# 5V_Buck.net
KiCad netlist of a schematic drawn in Altium Designer
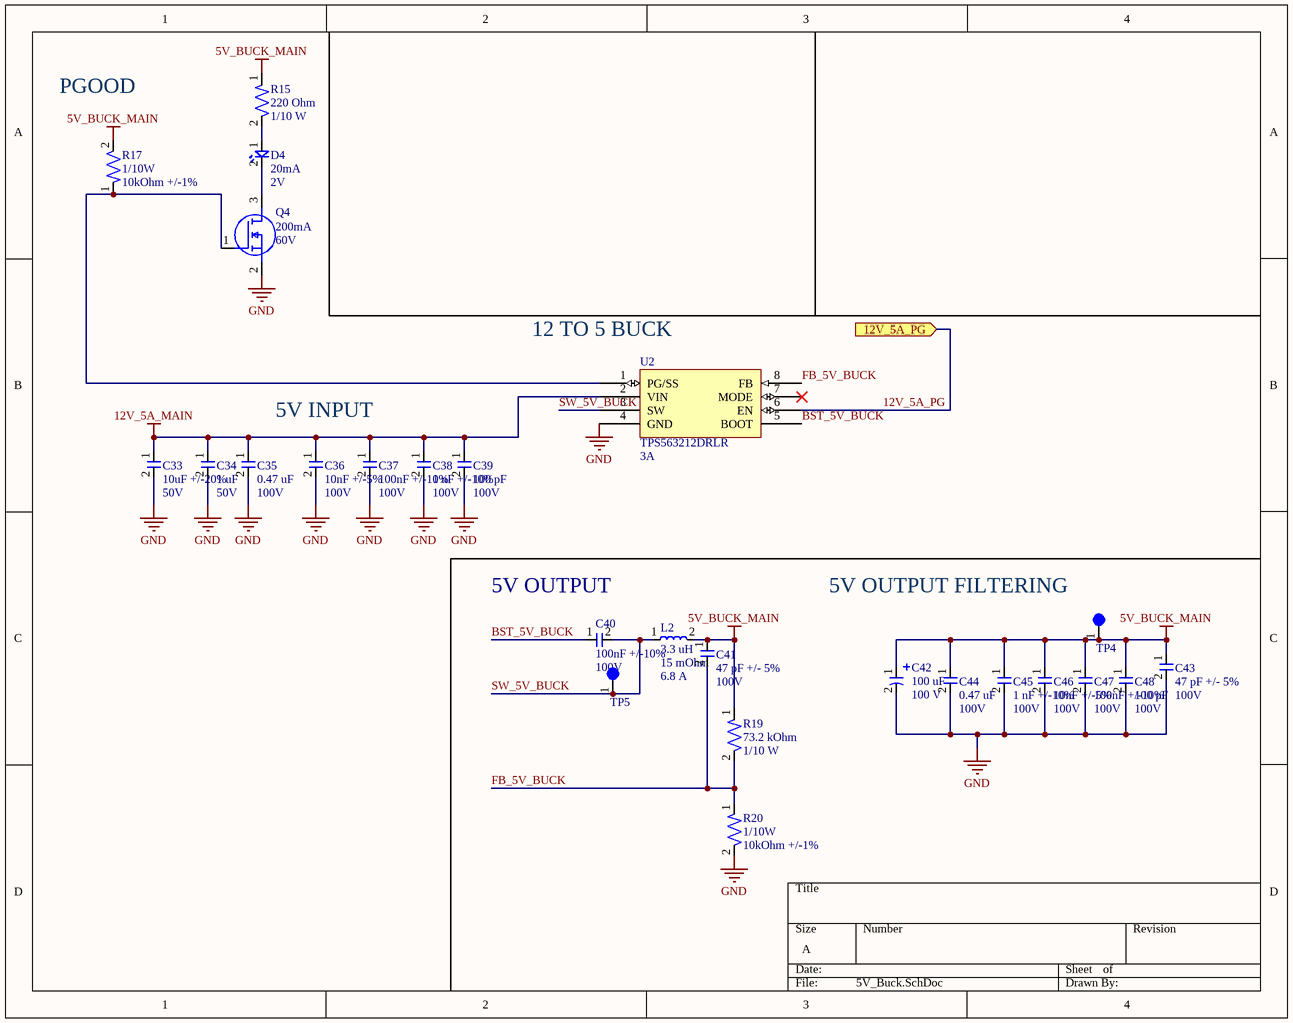
[diagram p0: 5V_Buck.SchDoc]

(export (version "E")
  (design (tool "Eeschema 10.0.6"))
  (components
    (comp (ref "C33")
      (value "CL31B106KBHNNNE")
      (footprint "CAP-1206")
      (description "10 µF ±10% 50V Ceramic Capacitor X7R 1206 (3216 Metric)")
      (fields
        (field (name "MANUFACTURER") "Samsung Electro-Mechanics")
        (field (name "CAPACITANCE") "10uF +/-20%")
        (field (name "VOLTAGE RATING") "50V")
      )
      (libsource (lib "MasterLib") (part "CAP-10U-0001"))
    )
    (comp (ref "C34")
      (value "UMK107AB7105KA-T")
      (footprint "CAP-0603")
      (description "1 µF ±10% 50V Ceramic Capacitor X7R 0603 (1608 Metric)")
      (fields (field (name "CAPACITANCE") "1 uF") (field (name "VOLTAGE") "50V"))
      (libsource (lib "MasterLib") (part "CAP-1U-0002"))
    )
    (comp (ref "C35")
      (value "KAM21KR72A474KL")
      (footprint "CAP-0805")
      (description "0.47 µF ±10% 100V Ceramic Capacitor X7R 0805 (2012 Metric)")
      (fields
        (field (name "TOLERANCE") "+/- 10%")
        (field (name "CAPACITANCE") "0.47 uF")
        (field (name "VOLTAGE") "100V")
      )
      (libsource (lib "MasterLib") (part "CAP-0.47U-0001"))
    )
    (comp (ref "C36")
      (value "C1608C0G2A103J080AC")
      (footprint "CAP-0603")
      (description "CAP CER 10000PF 100V C0G 0603")
      (fields
        (field (name "MANUFACTURER") "TDK Corporation")
        (field (name "CAPACITANCE") "10nF +/-5%")
        (field (name "VOLTAGE RATING") "100V")
      )
      (libsource (lib "MasterLib") (part "CAP-10N-0002"))
    )
    (comp (ref "C37")
      (value "CC0603KRX7R0BB104")
      (footprint "CAP-0603")
      (description "CAP CER 0.1UF 100V X7R 0603")
      (fields
        (field (name "MANUFACTURER") "YAGEO")
        (field (name "CAPACITANCE") "100nF +/-10%")
        (field (name "VOLTAGE RATING") "100V")
      )
      (libsource (lib "MasterLib") (part "CAP-100N-0001"))
    )
    (comp (ref "C38")
      (value "C0603Y102K1RAC7867")
      (footprint "CAP-0603")
      (description "1000 pF ±10% 100V Ceramic Capacitor X7R 0603 (1608 Metric)")
      (fields (field (name "CAPACITANCE") "1 nF +/-10%") (field (name "VOLTAGE") "100V"))
      (libsource (lib "MasterLib") (part "CAP-1N-0001"))
    )
    (comp (ref "C39")
      (value "0603N101J101CT")
      (footprint "CAP-0603")
      (description "100 pF ±5% 100V Ceramic Capacitor C0G, NP0 0603 (1608 Metric)")
      (fields
        (field (name "TOLERANCE") "+/-5%")
        (field (name "CAPACITANCE") "100 pF")
        (field (name "VOLTAGE") "100V")
      )
      (libsource (lib "MasterLib") (part "CAP-100P-0002"))
    )
    (comp (ref "C40")
      (value "CC0603KRX7R0BB104")
      (footprint "CAP-0603")
      (description "CAP CER 0.1UF 100V X7R 0603")
      (fields
        (field (name "MANUFACTURER") "YAGEO")
        (field (name "CAPACITANCE") "100nF +/-10%")
        (field (name "VOLTAGE RATING") "100V")
      )
      (libsource (lib "MasterLib") (part "CAP-100N-0001"))
    )
    (comp (ref "C41")
      (value "7447798111")
      (footprint "CAP-0603")
      (description "47 pF ±5% 100V Ceramic Capacitor C0G, NP0 0603 (1608 Metric)")
      (fields (field (name "CAPACITANCE") "47 pF +/- 5%") (field (name "VOLTAGE RATING") "100V"))
      (libsource (lib "MasterLib") (part "CAP-47P-0001"))
    )
    (comp (ref "C42")
      (value "100SEV100M12.5X16")
      (footprint "ELEC-100U-0001")
      (description "100 µF 100 V Aluminum Electrolytic Capacitors Radial, Can - SMD 2000 Hrs @ 85°C")
      (fields
        (field (name "MANUFACTURER") "Rubycon")
        (field (name "TOLERANCE") "+/- 20%")
        (field (name "CAPACITANCE") "100 uF")
        (field (name "VOLTAGE") "100 V")
      )
      (libsource (lib "MasterLib") (part "ELEC-100U-0001"))
    )
    (comp (ref "C43")
      (value "7447798111")
      (footprint "CAP-0603")
      (description "47 pF ±5% 100V Ceramic Capacitor C0G, NP0 0603 (1608 Metric)")
      (fields (field (name "CAPACITANCE") "47 pF +/- 5%") (field (name "VOLTAGE RATING") "100V"))
      (libsource (lib "MasterLib") (part "CAP-47P-0001"))
    )
    (comp (ref "C44")
      (value "KAM21KR72A474KL")
      (footprint "CAP-0805")
      (description "0.47 µF ±10% 100V Ceramic Capacitor X7R 0805 (2012 Metric)")
      (fields
        (field (name "TOLERANCE") "+/- 10%")
        (field (name "CAPACITANCE") "0.47 uF")
        (field (name "VOLTAGE") "100V")
      )
      (libsource (lib "MasterLib") (part "CAP-0.47U-0001"))
    )
    (comp (ref "C45")
      (value "C0603Y102K1RAC7867")
      (footprint "CAP-0603")
      (description "1000 pF ±10% 100V Ceramic Capacitor X7R 0603 (1608 Metric)")
      (fields (field (name "CAPACITANCE") "1 nF +/-10%") (field (name "VOLTAGE") "100V"))
      (libsource (lib "MasterLib") (part "CAP-1N-0001"))
    )
    (comp (ref "C46")
      (value "C1608C0G2A103J080AC")
      (footprint "CAP-0603")
      (description "CAP CER 10000PF 100V C0G 0603")
      (fields
        (field (name "MANUFACTURER") "TDK Corporation")
        (field (name "CAPACITANCE") "10nF +/-5%")
        (field (name "VOLTAGE RATING") "100V")
      )
      (libsource (lib "MasterLib") (part "CAP-10N-0002"))
    )
    (comp (ref "C47")
      (value "CC0603KRX7R0BB104")
      (footprint "CAP-0603")
      (description "CAP CER 0.1UF 100V X7R 0603")
      (fields
        (field (name "MANUFACTURER") "YAGEO")
        (field (name "CAPACITANCE") "100nF +/-10%")
        (field (name "VOLTAGE RATING") "100V")
      )
      (libsource (lib "MasterLib") (part "CAP-100N-0001"))
    )
    (comp (ref "C48")
      (value "0603N101J101CT")
      (footprint "CAP-0603")
      (description "100 pF ±5% 100V Ceramic Capacitor C0G, NP0 0603 (1608 Metric)")
      (fields
        (field (name "TOLERANCE") "+/-5%")
        (field (name "CAPACITANCE") "100 pF")
        (field (name "VOLTAGE") "100V")
      )
      (libsource (lib "MasterLib") (part "CAP-100P-0002"))
    )
    (comp (ref "D4")
      (value "150060AS75000")
      (footprint "LED-0603")
      (description "CAP CER 0.1UF 100V X7R 0603")
      (fields
        (field (name "MANUFACTURER") "Wurth Electronik")
        (field (name "CURRENT RATING") "20mA")
        (field (name "VF") "2V")
      )
      (libsource (lib "MasterLib") (part "LED_Amber_0001"))
    )
    (comp (ref "L2")
      (value "SRR1240-3R3Y")
      (footprint "PWRIND-3.3U-0003")
      (description "3.3 µH Shielded Drum Core, Wirewound Inductor 6.8 A 15mOhm Max Nonstandard")
      (fields
        (field (name "TOLERANCE") "30%")
        (field (name "INDUCTANCE") "3.3 uH")
        (field (name "DCR") "15 mOhm")
        (field (name "DCI") "6.8 A")
      )
      (libsource (lib "MasterLib") (part "PWRIND-3.3U-0003"))
    )
    (comp (ref "Q4")
      (value "T2N7002AK,LM")
      (footprint "NMOS-SOT23-3")
      (description "MOSFET N-CH 60V 200MA SOT23")
      (fields
        (field (name "MANUFACTURER") "Toshiba")
        (field (name "ID-CONTINUOUS") "200mA")
        (field (name "VDS-MAX") "60V")
      )
      (libsource (lib "MasterLib") (part "NMOS-200MA-0001"))
    )
    (comp (ref "R15")
      (value "CRGCQ0603J220R")
      (footprint "RES-0603")
      (fields
        (field (name "TOLERANCE") "+/- 5%")
        (field (name "RESISTANCE") "220 Ohm")
        (field (name "POWER") "1/10 W")
      )
      (libsource (lib "MasterLib") (part "RES-220-003"))
    )
    (comp (ref "R17")
      (value "RC0603FR-0710KP")
      (footprint "RES-0603")
      (description "RES SMD 10K OHM 1% 1/10W 0603")
      (fields
        (field (name "MANUFACTURER") "YAGEO")
        (field (name "POWER RATING") "1/10W")
        (field (name "RESISTANCE") "10kOhm +/-1%")
      )
      (libsource (lib "MasterLib") (part "RES-10K-0002"))
    )
    (comp (ref "R19")
      (value "RC0603FR-0773K2L")
      (footprint "RES-0603")
      (description "73.2 kOhms ±1% 0.1W, 1/10W Chip Resistor 0603 (1608 Metric) Moisture Resistant Thick Film")
      (fields
        (field (name "TOLERANCE") "1%")
        (field (name "RESISTANCE") "73.2 kOhm")
        (field (name "POWER") "1/10 W")
      )
      (libsource (lib "MasterLib") (part "RES-73.2K-0001"))
    )
    (comp (ref "R20")
      (value "RC0603FR-0710KP")
      (footprint "RES-0603")
      (description "RES SMD 10K OHM 1% 1/10W 0603")
      (fields
        (field (name "MANUFACTURER") "YAGEO")
        (field (name "POWER RATING") "1/10W")
        (field (name "RESISTANCE") "10kOhm +/-1%")
      )
      (libsource (lib "MasterLib") (part "RES-10K-0002"))
    )
    (comp (ref "TP4")
      (value "5003")
      (footprint "TEST-POINT-0001")
      (description "Oranange PC Test Point, Miniature Phoisphor Bronze Silver Plating Through Hole Mounting Type")
      (libsource (lib "MasterLib") (part "TEST-POINT-0001"))
    )
    (comp (ref "TP5")
      (value "5003")
      (footprint "TEST-POINT-0001")
      (description "Oranange PC Test Point, Miniature Phoisphor Bronze Silver Plating Through Hole Mounting Type")
      (libsource (lib "MasterLib") (part "TEST-POINT-0001"))
    )
    (comp (ref "U2")
      (value "TPS563212DRLR")
      (footprint "IC-SOT583")
      (description "Buck Switching Regulator IC Positive Adjustable 0.6V 1 Output 3A SOT-583")
      (fields (field (name "MANUFACTURER") "Texaas Instruments") (field (name "CURRENT") "3A"))
      (libsource (lib "MasterLib") (part "IC-BUCK-0008"))
    )
  )
  (nets
    (net (code "1") (name "/12V_5A_PG") (class "Default")
      (node (ref "U2") (pin "6") (pinfunction "EN_6") (pintype "bidirectional"))
    )
    (net (code "2") (name "/BST_5V_BUCK") (class "Default")
      (node (ref "C40") (pin "1") (pinfunction "1_1") (pintype "passive"))
      (node (ref "U2") (pin "5") (pinfunction "BOOT_5") (pintype "power_in"))
    )
    (net (code "3") (name "/FB_5V_BUCK") (class "Default")
      (node (ref "C41") (pin "2") (pinfunction "2_2") (pintype "passive"))
      (node (ref "R19") (pin "2") (pinfunction "2_2") (pintype "passive"))
      (node (ref "R20") (pin "1") (pinfunction "1_1") (pintype "passive"))
      (node (ref "U2") (pin "8") (pinfunction "FB_8") (pintype "input"))
    )
    (net (code "4") (name "/SW_5V_BUCK") (class "Default")
      (node (ref "C40") (pin "2") (pinfunction "2_2") (pintype "passive"))
      (node (ref "L2") (pin "1") (pinfunction "1_1") (pintype "passive"))
      (node (ref "TP5") (pin "1") (pinfunction "0_1") (pintype "passive"))
      (node (ref "U2") (pin "3") (pinfunction "SW_3") (pintype "power_in"))
    )
    (net (code "5") (name "5V_BUCK_MAIN") (class "Default")
      (node (ref "C41") (pin "1") (pinfunction "1_1") (pintype "passive"))
      (node (ref "C42") (pin "1") (pinfunction "1_1") (pintype "passive"))
      (node (ref "C43") (pin "1") (pinfunction "1_1") (pintype "passive"))
      (node (ref "C44") (pin "1") (pinfunction "1_1") (pintype "passive"))
      (node (ref "C45") (pin "1") (pinfunction "1_1") (pintype "passive"))
      (node (ref "C46") (pin "1") (pinfunction "1_1") (pintype "passive"))
      (node (ref "C47") (pin "1") (pinfunction "1_1") (pintype "passive"))
      (node (ref "C48") (pin "1") (pinfunction "1_1") (pintype "passive"))
      (node (ref "L2") (pin "2") (pinfunction "2_2") (pintype "passive"))
      (node (ref "R15") (pin "1") (pinfunction "1_1") (pintype "passive"))
      (node (ref "R17") (pin "2") (pinfunction "2_2") (pintype "passive"))
      (node (ref "R19") (pin "1") (pinfunction "1_1") (pintype "passive"))
      (node (ref "TP4") (pin "1") (pinfunction "0_1") (pintype "passive"))
    )
    (net (code "6") (name "12V_5A_MAIN") (class "Default")
      (node (ref "C33") (pin "1") (pinfunction "1_1") (pintype "passive"))
      (node (ref "C34") (pin "1") (pinfunction "1_1") (pintype "passive"))
      (node (ref "C35") (pin "1") (pinfunction "1_1") (pintype "passive"))
      (node (ref "C36") (pin "1") (pinfunction "1_1") (pintype "passive"))
      (node (ref "C37") (pin "1") (pinfunction "1_1") (pintype "passive"))
      (node (ref "C38") (pin "1") (pinfunction "1_1") (pintype "passive"))
      (node (ref "C39") (pin "1") (pinfunction "1_1") (pintype "passive"))
      (node (ref "U2") (pin "2") (pinfunction "VIN_2") (pintype "power_in"))
    )
    (net (code "7") (name "GND") (class "Default")
      (node (ref "C33") (pin "2") (pinfunction "2_2") (pintype "passive"))
      (node (ref "C34") (pin "2") (pinfunction "2_2") (pintype "passive"))
      (node (ref "C35") (pin "2") (pinfunction "2_2") (pintype "passive"))
      (node (ref "C36") (pin "2") (pinfunction "2_2") (pintype "passive"))
      (node (ref "C37") (pin "2") (pinfunction "2_2") (pintype "passive"))
      (node (ref "C38") (pin "2") (pinfunction "2_2") (pintype "passive"))
      (node (ref "C39") (pin "2") (pinfunction "2_2") (pintype "passive"))
      (node (ref "C42") (pin "2") (pinfunction "2_2") (pintype "passive"))
      (node (ref "C43") (pin "2") (pinfunction "2_2") (pintype "passive"))
      (node (ref "C44") (pin "2") (pinfunction "2_2") (pintype "passive"))
      (node (ref "C45") (pin "2") (pinfunction "2_2") (pintype "passive"))
      (node (ref "C46") (pin "2") (pinfunction "2_2") (pintype "passive"))
      (node (ref "C47") (pin "2") (pinfunction "2_2") (pintype "passive"))
      (node (ref "C48") (pin "2") (pinfunction "2_2") (pintype "passive"))
      (node (ref "Q4") (pin "2") (pinfunction "S_2") (pintype "passive"))
      (node (ref "R20") (pin "2") (pinfunction "2_2") (pintype "passive"))
      (node (ref "U2") (pin "4") (pinfunction "GND_4") (pintype "power_in"))
    )
    (net (code "8") (name "Net-(D4-Pad1)") (class "Default")
      (node (ref "D4") (pin "1") (pinfunction "1_1") (pintype "passive"))
      (node (ref "R15") (pin "2") (pinfunction "2_2") (pintype "passive"))
    )
    (net (code "9") (name "Net-(Q4-D)") (class "Default")
      (node (ref "D4") (pin "2") (pinfunction "2_2") (pintype "passive"))
      (node (ref "Q4") (pin "3") (pinfunction "D_3") (pintype "passive"))
    )
    (net (code "10") (name "Net-(Q4-G)") (class "Default")
      (node (ref "Q4") (pin "1") (pinfunction "G_1") (pintype "passive"))
      (node (ref "R17") (pin "1") (pinfunction "1_1") (pintype "passive"))
      (node (ref "U2") (pin "1") (pinfunction "PG/SS_1") (pintype "bidirectional"))
    )
    (net (code "11") (name "unconnected-(U2-MODE-Pad7)") (class "Default")
      (node (ref "U2") (pin "7") (pinfunction "MODE_7") (pintype "bidirectional+no_connect"))
    )
  )
)
